# main.net
KiCad netlist of a schematic drawn in EAGLE
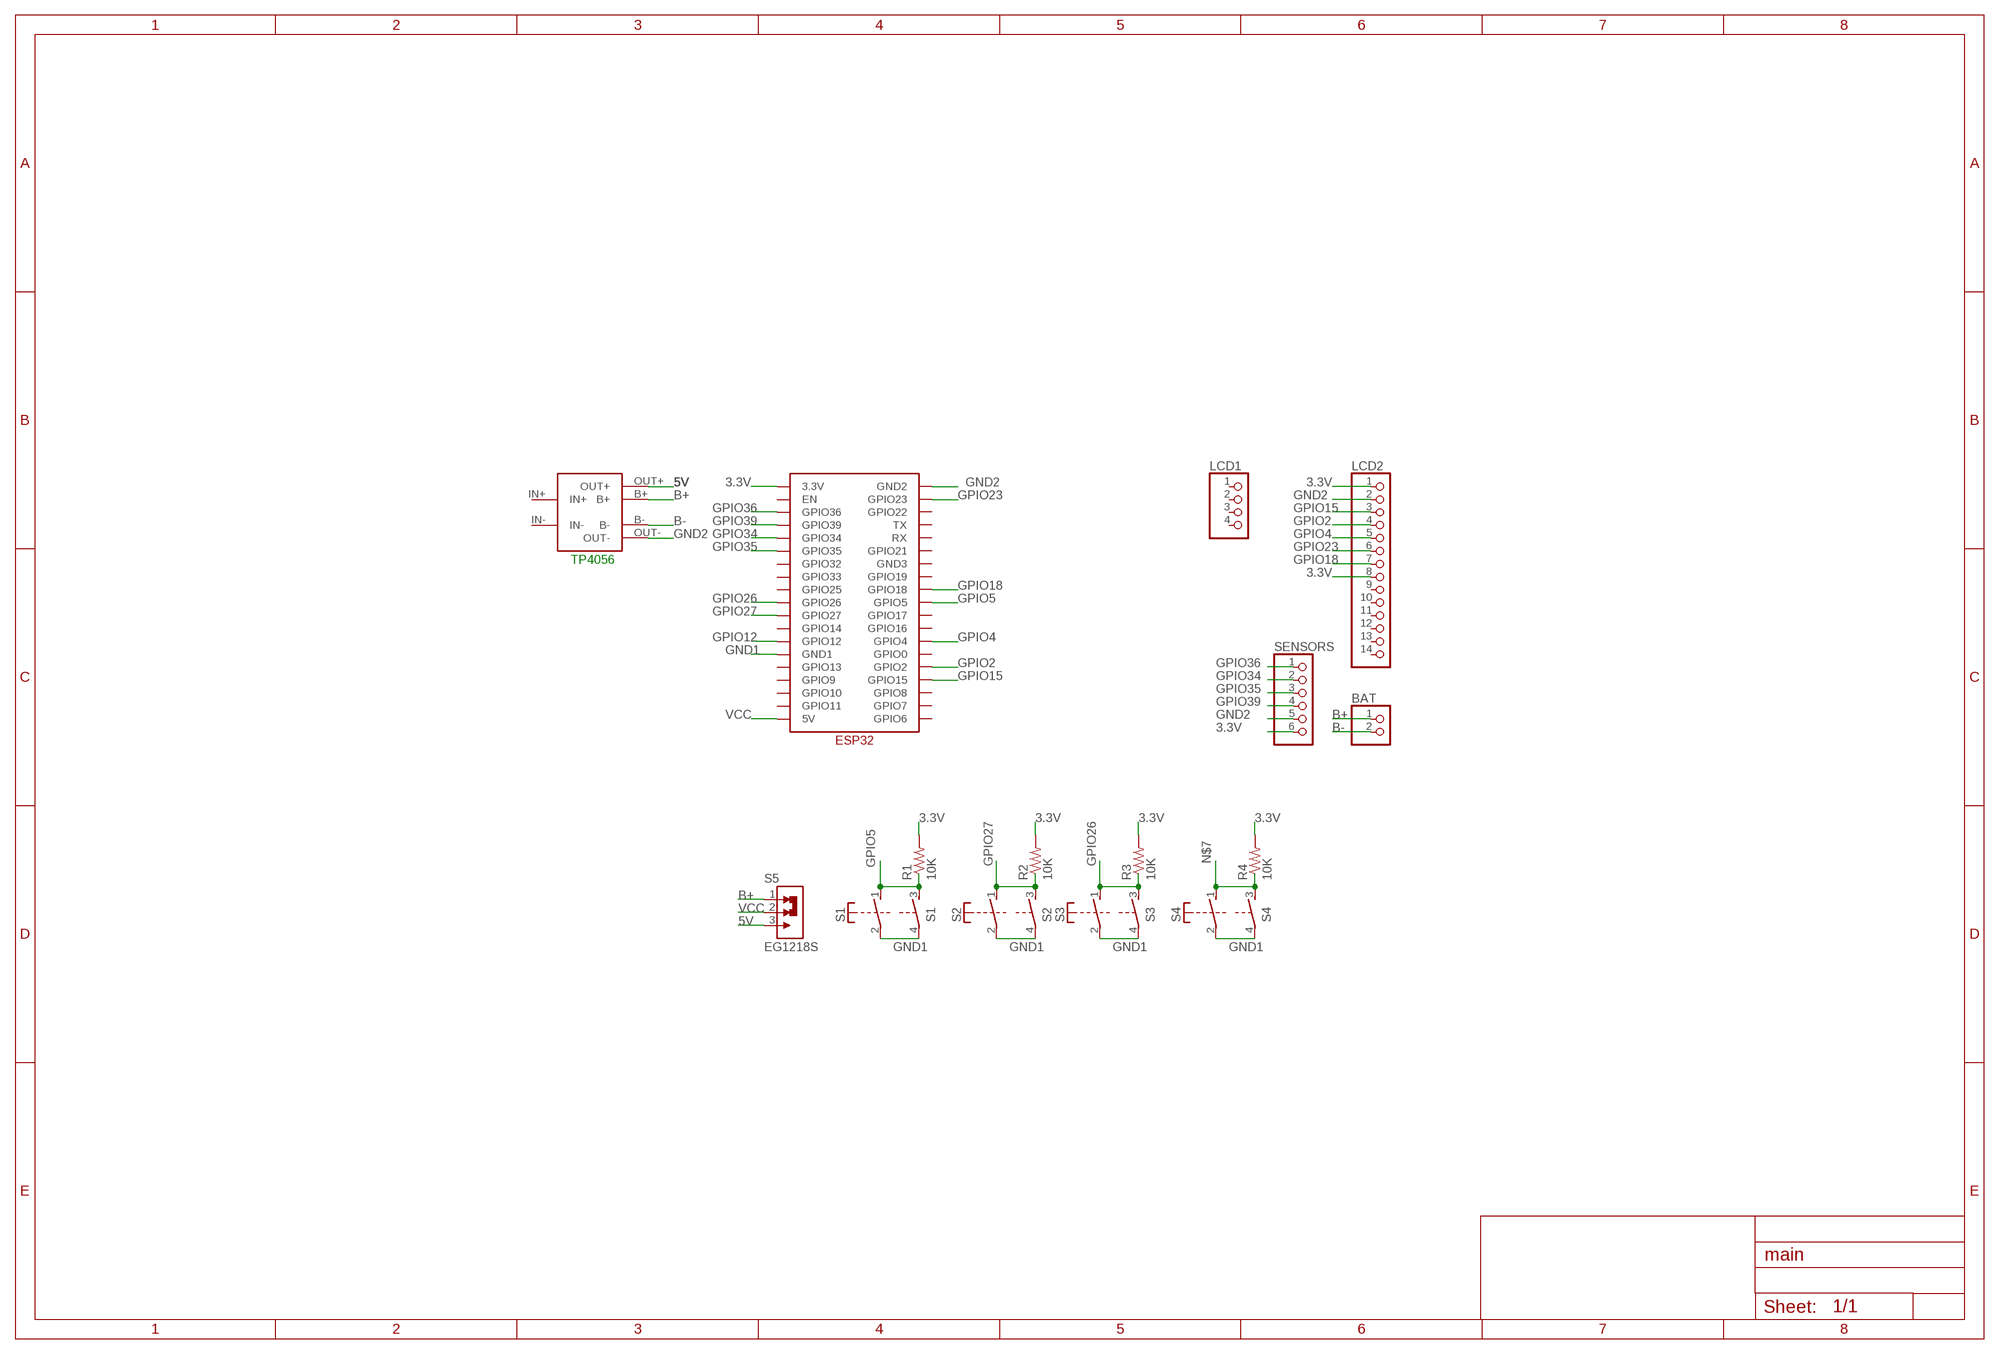
[diagram p0: schematic, sheet 1]

(export (version "E")
  (design (tool "Eeschema 10.0.6"))
  (components
    (comp (ref "BAT")
      (value "PINHD-1X2")
      (footprint "eagle-import:1X02")
      (libsource (lib "eagle-import") (part "PINHD-1X2"))
    )
    (comp (ref "LCD1")
      (value "PINHD-1X4")
      (footprint "eagle-import:1X04")
      (libsource (lib "eagle-import") (part "PINHD-1X4"))
    )
    (comp (ref "LCD2")
      (value "PINHD-1X14")
      (footprint "eagle-import:1X14")
      (libsource (lib "eagle-import") (part "PINHD-1X14"))
    )
    (comp (ref "R1")
      (value "10K")
      (footprint "eagle-import:R0603")
      (libsource (lib "eagle-import") (part "R-US_R0603"))
    )
    (comp (ref "R2")
      (value "10K")
      (footprint "eagle-import:R0603")
      (libsource (lib "eagle-import") (part "R-US_R0603"))
    )
    (comp (ref "R3")
      (value "10K")
      (footprint "eagle-import:R0603")
      (libsource (lib "eagle-import") (part "R-US_R0603"))
    )
    (comp (ref "R4")
      (value "10K")
      (footprint "eagle-import:R0603")
      (libsource (lib "eagle-import") (part "R-US_R0603"))
    )
    (comp (ref "S1")
      (value "PVA1")
      (footprint "eagle-import:PVA1F")
      (libsource (lib "eagle-import") (part "PVA1"))
    )
    (comp (ref "S2")
      (value "PVA1")
      (footprint "eagle-import:PVA1F")
      (libsource (lib "eagle-import") (part "PVA1"))
    )
    (comp (ref "S3")
      (value "PVA1")
      (footprint "eagle-import:PVA1F")
      (libsource (lib "eagle-import") (part "PVA1"))
    )
    (comp (ref "S4")
      (value "PVA1")
      (footprint "eagle-import:PVA1F")
      (libsource (lib "eagle-import") (part "PVA1"))
    )
    (comp (ref "S5")
      (value "EG1218S")
      (footprint "eagle-import:SW_EG1218")
      (fields (field (name "MF") "E-Switch") (field (name "MP") "EG1218"))
      (libsource (lib "eagle-import") (part "EG1218S"))
    )
    (comp (ref "SENSORS")
      (value "PINHD-1X6")
      (footprint "eagle-import:1X06")
      (libsource (lib "eagle-import") (part "PINHD-1X6"))
    )
    (comp (ref "U$1")
      (value "TP4056-PTH")
      (footprint "eagle-import:TP4056-PTH")
      (libsource (lib "eagle-import") (part "TP4056-PTH"))
    )
    (comp (ref "U$2")
      (value "ESP32")
      (footprint "eagle-import:ESP32")
      (libsource (lib "eagle-import") (part "ESP32"))
    )
  )
  (nets
    (net (code "1") (name "/3.3V") (class "Default")
      (node (ref "LCD2") (pin "1") (pinfunction "1_1") (pintype "passive"))
      (node (ref "LCD2") (pin "8") (pinfunction "8_8") (pintype "passive"))
      (node (ref "R1") (pin "2") (pinfunction "2_2") (pintype "passive"))
      (node (ref "R2") (pin "2") (pinfunction "2_2") (pintype "passive"))
      (node (ref "R3") (pin "2") (pinfunction "2_2") (pintype "passive"))
      (node (ref "R4") (pin "2") (pinfunction "2_2") (pintype "passive"))
      (node (ref "SENSORS") (pin "6") (pinfunction "6_6") (pintype "passive"))
      (node (ref "U$2") (pin "3.3V") (pinfunction "3.3V_3.3V") (pintype "bidirectional"))
    )
    (net (code "2") (name "/5V") (class "Default")
      (node (ref "S5") (pin "3") (pinfunction "NO_3") (pintype "passive"))
      (node (ref "U$1") (pin "OUT+") (pinfunction "OUT+_OUT+") (pintype "bidirectional"))
    )
    (net (code "3") (name "/B+") (class "Default")
      (node (ref "BAT") (pin "1") (pinfunction "1_1") (pintype "passive"))
      (node (ref "S5") (pin "1") (pinfunction "NC_1") (pintype "passive"))
      (node (ref "U$1") (pin "B+") (pinfunction "B+_B+") (pintype "bidirectional"))
    )
    (net (code "4") (name "/B-") (class "Default")
      (node (ref "BAT") (pin "2") (pinfunction "2_2") (pintype "passive"))
      (node (ref "U$1") (pin "B-") (pinfunction "B-_B-") (pintype "bidirectional"))
    )
    (net (code "5") (name "/GND1") (class "Default")
      (node (ref "S1") (pin "2") (pinfunction "P_2") (pintype "passive"))
      (node (ref "S1") (pin "4") (pinfunction "P_4") (pintype "passive"))
      (node (ref "U$2") (pin "GND1") (pinfunction "GND1_GND1") (pintype "bidirectional"))
    )
    (net (code "6") (name "/GND2") (class "Default")
      (node (ref "LCD2") (pin "2") (pinfunction "2_2") (pintype "passive"))
      (node (ref "SENSORS") (pin "5") (pinfunction "5_5") (pintype "passive"))
      (node (ref "U$1") (pin "OUT-") (pinfunction "OUT-_OUT-") (pintype "bidirectional"))
      (node (ref "U$2") (pin "GND2") (pinfunction "GND2_GND2") (pintype "bidirectional"))
    )
    (net (code "7") (name "/GPIO2") (class "Default")
      (node (ref "LCD2") (pin "4") (pinfunction "4_4") (pintype "passive"))
      (node (ref "U$2") (pin "GPIO2") (pinfunction "GPIO2_GPIO2") (pintype "bidirectional"))
    )
    (net (code "8") (name "/GPIO4") (class "Default")
      (node (ref "LCD2") (pin "5") (pinfunction "5_5") (pintype "passive"))
      (node (ref "U$2") (pin "GPIO4") (pinfunction "GPIO4_GPIO4") (pintype "bidirectional"))
    )
    (net (code "9") (name "/GPIO5") (class "Default")
      (node (ref "R1") (pin "1") (pinfunction "1_1") (pintype "passive"))
      (node (ref "S1") (pin "1") (pinfunction "S_1") (pintype "passive"))
      (node (ref "S1") (pin "3") (pinfunction "S_3") (pintype "passive"))
      (node (ref "U$2") (pin "GPIO5") (pinfunction "GPIO5_GPIO5") (pintype "bidirectional"))
    )
    (net (code "10") (name "/GPIO12") (class "Default")
      (node (ref "U$2") (pin "GPIO12") (pinfunction "GPIO12_GPIO12") (pintype "bidirectional"))
    )
    (net (code "11") (name "/GPIO15") (class "Default")
      (node (ref "LCD2") (pin "3") (pinfunction "3_3") (pintype "passive"))
      (node (ref "U$2") (pin "GPIO15") (pinfunction "GPIO15_GPIO15") (pintype "bidirectional"))
    )
    (net (code "12") (name "/GPIO18") (class "Default")
      (node (ref "LCD2") (pin "7") (pinfunction "7_7") (pintype "passive"))
      (node (ref "U$2") (pin "GPIO18") (pinfunction "GPIO18_GPIO18") (pintype "bidirectional"))
    )
    (net (code "13") (name "/GPIO23") (class "Default")
      (node (ref "LCD2") (pin "6") (pinfunction "6_6") (pintype "passive"))
      (node (ref "U$2") (pin "GPIO23") (pinfunction "GPIO23_GPIO23") (pintype "bidirectional"))
    )
    (net (code "14") (name "/GPIO26") (class "Default")
      (node (ref "R3") (pin "1") (pinfunction "1_1") (pintype "passive"))
      (node (ref "S3") (pin "1") (pinfunction "S_1") (pintype "passive"))
      (node (ref "S3") (pin "3") (pinfunction "S_3") (pintype "passive"))
      (node (ref "U$2") (pin "GPIO26") (pinfunction "GPIO26_GPIO26") (pintype "bidirectional"))
    )
    (net (code "15") (name "/GPIO27") (class "Default")
      (node (ref "R2") (pin "1") (pinfunction "1_1") (pintype "passive"))
      (node (ref "S2") (pin "1") (pinfunction "S_1") (pintype "passive"))
      (node (ref "S2") (pin "3") (pinfunction "S_3") (pintype "passive"))
      (node (ref "U$2") (pin "GPIO27") (pinfunction "GPIO27_GPIO27") (pintype "bidirectional"))
    )
    (net (code "16") (name "/GPIO34") (class "Default")
      (node (ref "SENSORS") (pin "2") (pinfunction "2_2") (pintype "passive"))
      (node (ref "U$2") (pin "GPIO34") (pinfunction "GPIO34_GPIO34") (pintype "bidirectional"))
    )
    (net (code "17") (name "/GPIO35") (class "Default")
      (node (ref "SENSORS") (pin "3") (pinfunction "3_3") (pintype "passive"))
      (node (ref "U$2") (pin "GPIO35") (pinfunction "GPIO35_GPIO35") (pintype "bidirectional"))
    )
    (net (code "18") (name "/GPIO36") (class "Default")
      (node (ref "SENSORS") (pin "1") (pinfunction "1_1") (pintype "passive"))
      (node (ref "U$2") (pin "GPIO36") (pinfunction "GPIO36_GPIO36") (pintype "bidirectional"))
    )
    (net (code "19") (name "/GPIO39") (class "Default")
      (node (ref "SENSORS") (pin "4") (pinfunction "4_4") (pintype "passive"))
      (node (ref "U$2") (pin "GPIO39") (pinfunction "GPIO39_GPIO39") (pintype "bidirectional"))
    )
    (net (code "20") (name "/N$7") (class "Default")
      (node (ref "R4") (pin "1") (pinfunction "1_1") (pintype "passive"))
      (node (ref "S4") (pin "1") (pinfunction "S_1") (pintype "passive"))
      (node (ref "S4") (pin "3") (pinfunction "S_3") (pintype "passive"))
    )
    (net (code "21") (name "/VCC") (class "Default")
      (node (ref "S5") (pin "2") (pinfunction "COM_2") (pintype "passive"))
      (node (ref "U$2") (pin "5V") (pinfunction "5V_5V") (pintype "bidirectional"))
    )
    (net (code "22") (name "Net-(S2A-P)") (class "Default")
      (node (ref "S2") (pin "2") (pinfunction "P_2") (pintype "passive"))
      (node (ref "S2") (pin "4") (pinfunction "P_4") (pintype "passive"))
    )
    (net (code "23") (name "Net-(S3A-P)") (class "Default")
      (node (ref "S3") (pin "2") (pinfunction "P_2") (pintype "passive"))
      (node (ref "S3") (pin "4") (pinfunction "P_4") (pintype "passive"))
    )
    (net (code "24") (name "Net-(S4A-P)") (class "Default")
      (node (ref "S4") (pin "2") (pinfunction "P_2") (pintype "passive"))
      (node (ref "S4") (pin "4") (pinfunction "P_4") (pintype "passive"))
    )
    (net (code "25") (name "unconnected-(LCD1-Pad1)") (class "Default")
      (node (ref "LCD1") (pin "1") (pinfunction "1_1") (pintype "passive"))
    )
    (net (code "26") (name "unconnected-(LCD1-Pad2)") (class "Default")
      (node (ref "LCD1") (pin "2") (pinfunction "2_2") (pintype "passive"))
    )
    (net (code "27") (name "unconnected-(LCD1-Pad3)") (class "Default")
      (node (ref "LCD1") (pin "3") (pinfunction "3_3") (pintype "passive"))
    )
    (net (code "28") (name "unconnected-(LCD1-Pad4)") (class "Default")
      (node (ref "LCD1") (pin "4") (pinfunction "4_4") (pintype "passive"))
    )
    (net (code "29") (name "unconnected-(LCD2-Pad9)") (class "Default")
      (node (ref "LCD2") (pin "9") (pinfunction "9_9") (pintype "passive"))
    )
    (net (code "30") (name "unconnected-(LCD2-Pad10)") (class "Default")
      (node (ref "LCD2") (pin "10") (pinfunction "10_10") (pintype "passive"))
    )
    (net (code "31") (name "unconnected-(LCD2-Pad11)") (class "Default")
      (node (ref "LCD2") (pin "11") (pinfunction "11_11") (pintype "passive"))
    )
    (net (code "32") (name "unconnected-(LCD2-Pad12)") (class "Default")
      (node (ref "LCD2") (pin "12") (pinfunction "12_12") (pintype "passive"))
    )
    (net (code "33") (name "unconnected-(LCD2-Pad13)") (class "Default")
      (node (ref "LCD2") (pin "13") (pinfunction "13_13") (pintype "passive"))
    )
    (net (code "34") (name "unconnected-(LCD2-Pad14)") (class "Default")
      (node (ref "LCD2") (pin "14") (pinfunction "14_14") (pintype "passive"))
    )
    (net (code "35") (name "unconnected-(U$1-PadIN+)") (class "Default")
      (node (ref "U$1") (pin "IN+") (pinfunction "IN+_IN+") (pintype "bidirectional"))
    )
    (net (code "36") (name "unconnected-(U$1-PadIN-)") (class "Default")
      (node (ref "U$1") (pin "IN-") (pinfunction "IN-_IN-") (pintype "bidirectional"))
    )
    (net (code "37") (name "unconnected-(U$2-PadEN)") (class "Default")
      (node (ref "U$2") (pin "EN") (pinfunction "EN_EN") (pintype "bidirectional"))
    )
    (net (code "38") (name "unconnected-(U$2-PadGND3)") (class "Default")
      (node (ref "U$2") (pin "GND3") (pinfunction "GND3_GND3") (pintype "bidirectional"))
    )
    (net (code "39") (name "unconnected-(U$2-PadGPIO0)") (class "Default")
      (node (ref "U$2") (pin "GPIO0") (pinfunction "GPIO0_GPIO0") (pintype "bidirectional"))
    )
    (net (code "40") (name "unconnected-(U$2-PadGPIO6)") (class "Default")
      (node (ref "U$2") (pin "GPIO6") (pinfunction "GPIO6_GPIO6") (pintype "bidirectional"))
    )
    (net (code "41") (name "unconnected-(U$2-PadGPIO7)") (class "Default")
      (node (ref "U$2") (pin "GPIO7") (pinfunction "GPIO7_GPIO7") (pintype "bidirectional"))
    )
    (net (code "42") (name "unconnected-(U$2-PadGPIO8)") (class "Default")
      (node (ref "U$2") (pin "GPIO8") (pinfunction "GPIO8_GPIO8") (pintype "bidirectional"))
    )
    (net (code "43") (name "unconnected-(U$2-PadGPIO9)") (class "Default")
      (node (ref "U$2") (pin "GPIO9") (pinfunction "GPIO9_GPIO9") (pintype "bidirectional"))
    )
    (net (code "44") (name "unconnected-(U$2-PadGPIO10)") (class "Default")
      (node (ref "U$2") (pin "GPIO10") (pinfunction "GPIO10_GPIO10") (pintype "bidirectional"))
    )
    (net (code "45") (name "unconnected-(U$2-PadGPIO11)") (class "Default")
      (node (ref "U$2") (pin "GPIO11") (pinfunction "GPIO11_GPIO11") (pintype "bidirectional"))
    )
    (net (code "46") (name "unconnected-(U$2-PadGPIO13)") (class "Default")
      (node (ref "U$2") (pin "GPIO13") (pinfunction "GPIO13_GPIO13") (pintype "bidirectional"))
    )
    (net (code "47") (name "unconnected-(U$2-PadGPIO14)") (class "Default")
      (node (ref "U$2") (pin "GPIO14") (pinfunction "GPIO14_GPIO14") (pintype "bidirectional"))
    )
    (net (code "48") (name "unconnected-(U$2-PadGPIO16)") (class "Default")
      (node (ref "U$2") (pin "GPIO16") (pinfunction "GPIO16_GPIO16") (pintype "bidirectional"))
    )
    (net (code "49") (name "unconnected-(U$2-PadGPIO17)") (class "Default")
      (node (ref "U$2") (pin "GPIO17") (pinfunction "GPIO17_GPIO17") (pintype "bidirectional"))
    )
    (net (code "50") (name "unconnected-(U$2-PadGPIO19)") (class "Default")
      (node (ref "U$2") (pin "GPIO19") (pinfunction "GPIO19_GPIO19") (pintype "bidirectional"))
    )
    (net (code "51") (name "unconnected-(U$2-PadGPIO21)") (class "Default")
      (node (ref "U$2") (pin "GPIO21") (pinfunction "GPIO21_GPIO21") (pintype "bidirectional"))
    )
    (net (code "52") (name "unconnected-(U$2-PadGPIO22)") (class "Default")
      (node (ref "U$2") (pin "GPIO22") (pinfunction "GPIO22_GPIO22") (pintype "bidirectional"))
    )
    (net (code "53") (name "unconnected-(U$2-PadGPIO25)") (class "Default")
      (node (ref "U$2") (pin "GPIO25") (pinfunction "GPIO25_GPIO25") (pintype "bidirectional"))
    )
    (net (code "54") (name "unconnected-(U$2-PadGPIO32)") (class "Default")
      (node (ref "U$2") (pin "GPIO32") (pinfunction "GPIO32_GPIO32") (pintype "bidirectional"))
    )
    (net (code "55") (name "unconnected-(U$2-PadGPIO33)") (class "Default")
      (node (ref "U$2") (pin "GPIO33") (pinfunction "GPIO33_GPIO33") (pintype "bidirectional"))
    )
    (net (code "56") (name "unconnected-(U$2-PadRX)") (class "Default")
      (node (ref "U$2") (pin "RX") (pinfunction "RX_RX") (pintype "bidirectional"))
    )
    (net (code "57") (name "unconnected-(U$2-PadTX)") (class "Default")
      (node (ref "U$2") (pin "TX") (pinfunction "TX_TX") (pintype "bidirectional"))
    )
  )
)
